# PX4FMUv2_4_6_0.net
KiCad netlist of a schematic drawn in Altium Designer
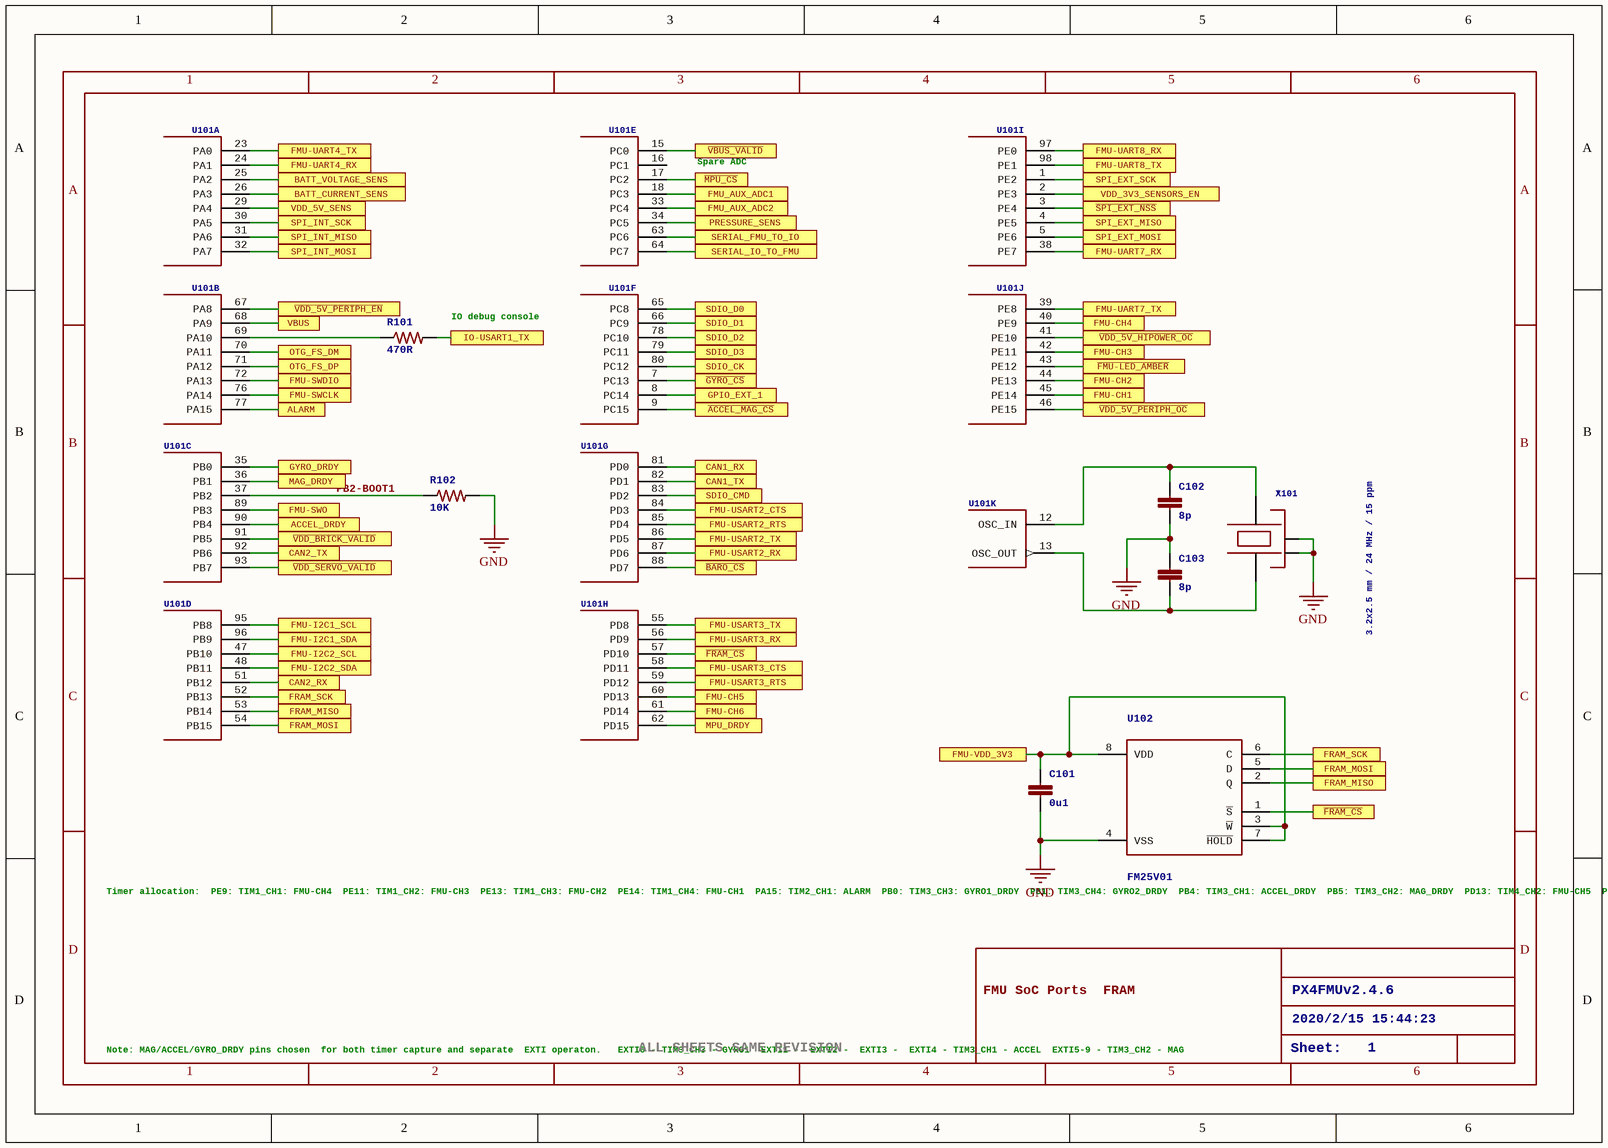
[diagram p0: PX4FMUv2.4.6_0.SchDoc]

(export (version "E")
  (design (tool "Eeschema 10.0.6"))
  (components
    (comp (ref "C101")
      (value "0u1")
      (footprint "0402-CAP")
      (description "CapacitorStandard 0603 ceramic capacitor, and 0.1\" leaded capacitor.")
      (fields (field (name "PARTNO") "CC0402ZRY5V7BB104"))
      (libsource (lib "pixhawk2") (part "CAP0402"))
    )
    (comp (ref "C102")
      (value "8p")
      (footprint "0402-CAP")
      (description "CapacitorStandard 0603 ceramic capacitor, and 0.1\" leaded capacitor.")
      (fields (field (name "PARTNO") "C1005C0G1H080C"))
      (libsource (lib "pixhawk2") (part "CAP0402"))
    )
    (comp (ref "C103")
      (value "8p")
      (footprint "0402-CAP")
      (description "CapacitorStandard 0603 ceramic capacitor, and 0.1\" leaded capacitor.")
      (fields (field (name "PARTNO") "C1005C0G1H080C"))
      (libsource (lib "pixhawk2") (part "CAP0402"))
    )
    (comp (ref "R101")
      (value "470R")
      (footprint "0402-RES")
      (fields (field (name "PARTNO") "RC0402FR-07470RL"))
      (libsource (lib "pixhawk2") (part "RESISTOR0402-RES"))
    )
    (comp (ref "R102")
      (value "10K")
      (footprint "0402-RES")
      (fields (field (name "PARTNO") "RC0402FR-0710KL"))
      (libsource (lib "pixhawk2") (part "RESISTOR0402-RES"))
    )
    (comp (ref "U101")
      (value "STM32F4X7VX")
      (footprint "TQFP100")
      (fields (field (name "PARTNO") "STM32F427VI"))
      (libsource (lib "pixhawk2") (part "STM32F4X7VX"))
    )
    (comp (ref "U102")
      (value "FM25V01")
      (footprint "SO08")
      (description "FM25V01 128Kb Serial 3V F-RAM Memory")
      (fields (field (name "PARTNO") "FM25V01-G"))
      (libsource (lib "pixhawk2") (part "FM25V01"))
    )
    (comp (ref "X101")
      (value "3.2x2.5 mm / 24 MHz / 15 ppm")
      (footprint "OSCILLATOR-3.2X2.5")
      (description "Crystal Oscillator in 3.2x2.5 SMD")
      (fields (field (name "NAME") "*") (field (name "PARTNO") "NX3225SA-24.000000MHZ"))
      (libsource (lib "pixhawk2") (part "OSCILLATOR-3.2X2.5"))
    )
  )
  (nets
    (net (code "1") (name "/ACCEL_DRDY") (class "Default")
      (node (ref "U101") (pin "90") (pinfunction "PB4_90") (pintype "passive"))
    )
    (net (code "2") (name "/ALARM") (class "Default")
      (node (ref "U101") (pin "77") (pinfunction "PA15_77") (pintype "passive"))
    )
    (net (code "3") (name "/BATT_CURRENT_SENS") (class "Default")
      (node (ref "U101") (pin "26") (pinfunction "PA3_26") (pintype "passive"))
    )
    (net (code "4") (name "/BATT_VOLTAGE_SENS") (class "Default")
      (node (ref "U101") (pin "25") (pinfunction "PA2_25") (pintype "passive"))
    )
    (net (code "5") (name "/CAN1_RX") (class "Default")
      (node (ref "U101") (pin "81") (pinfunction "PD0_81") (pintype "passive"))
    )
    (net (code "6") (name "/CAN1_TX") (class "Default")
      (node (ref "U101") (pin "82") (pinfunction "PD1_82") (pintype "passive"))
    )
    (net (code "7") (name "/CAN2_RX") (class "Default")
      (node (ref "U101") (pin "51") (pinfunction "PB12_51") (pintype "passive"))
    )
    (net (code "8") (name "/CAN2_TX") (class "Default")
      (node (ref "U101") (pin "92") (pinfunction "PB6_92") (pintype "passive"))
    )
    (net (code "9") (name "/FMU-CH1") (class "Default")
      (node (ref "U101") (pin "45") (pinfunction "PE14_45") (pintype "passive"))
    )
    (net (code "10") (name "/FMU-CH2") (class "Default")
      (node (ref "U101") (pin "44") (pinfunction "PE13_44") (pintype "passive"))
    )
    (net (code "11") (name "/FMU-CH3") (class "Default")
      (node (ref "U101") (pin "42") (pinfunction "PE11_42") (pintype "passive"))
    )
    (net (code "12") (name "/FMU-CH4") (class "Default")
      (node (ref "U101") (pin "40") (pinfunction "PE9_40") (pintype "passive"))
    )
    (net (code "13") (name "/FMU-CH5") (class "Default")
      (node (ref "U101") (pin "60") (pinfunction "PD13_60") (pintype "passive"))
    )
    (net (code "14") (name "/FMU-CH6") (class "Default")
      (node (ref "U101") (pin "61") (pinfunction "PD14_61") (pintype "passive"))
    )
    (net (code "15") (name "/FMU-I2C1_SCL") (class "Default")
      (node (ref "U101") (pin "95") (pinfunction "PB8_95") (pintype "passive"))
    )
    (net (code "16") (name "/FMU-I2C1_SDA") (class "Default")
      (node (ref "U101") (pin "96") (pinfunction "PB9_96") (pintype "passive"))
    )
    (net (code "17") (name "/FMU-I2C2_SCL") (class "Default")
      (node (ref "U101") (pin "47") (pinfunction "PB10_47") (pintype "passive"))
    )
    (net (code "18") (name "/FMU-I2C2_SDA") (class "Default")
      (node (ref "U101") (pin "48") (pinfunction "PB11_48") (pintype "passive"))
    )
    (net (code "19") (name "/FMU-SWCLK") (class "Default")
      (node (ref "U101") (pin "76") (pinfunction "PA14_76") (pintype "passive"))
    )
    (net (code "20") (name "/FMU-SWDIO") (class "Default")
      (node (ref "U101") (pin "72") (pinfunction "PA13_72") (pintype "passive"))
    )
    (net (code "21") (name "/FMU-SWO") (class "Default")
      (node (ref "U101") (pin "89") (pinfunction "PB3_89") (pintype "passive"))
    )
    (net (code "22") (name "/FMU-UART4_RX") (class "Default")
      (node (ref "U101") (pin "24") (pinfunction "PA1_24") (pintype "passive"))
    )
    (net (code "23") (name "/FMU-UART4_TX") (class "Default")
      (node (ref "U101") (pin "23") (pinfunction "PA0_23") (pintype "passive"))
    )
    (net (code "24") (name "/FMU-UART7_RX") (class "Default")
      (node (ref "U101") (pin "38") (pinfunction "PE7_38") (pintype "passive"))
    )
    (net (code "25") (name "/FMU-UART7_TX") (class "Default")
      (node (ref "U101") (pin "39") (pinfunction "PE8_39") (pintype "passive"))
    )
    (net (code "26") (name "/FMU-UART8_RX") (class "Default")
      (node (ref "U101") (pin "97") (pinfunction "PE0_97") (pintype "passive"))
    )
    (net (code "27") (name "/FMU-UART8_TX") (class "Default")
      (node (ref "U101") (pin "98") (pinfunction "PE1_98") (pintype "passive"))
    )
    (net (code "28") (name "/FMU-USART2_CTS") (class "Default")
      (node (ref "U101") (pin "84") (pinfunction "PD3_84") (pintype "passive"))
    )
    (net (code "29") (name "/FMU-USART2_RTS") (class "Default")
      (node (ref "U101") (pin "85") (pinfunction "PD4_85") (pintype "passive"))
    )
    (net (code "30") (name "/FMU-USART2_RX") (class "Default")
      (node (ref "U101") (pin "87") (pinfunction "PD6_87") (pintype "passive"))
    )
    (net (code "31") (name "/FMU-USART2_TX") (class "Default")
      (node (ref "U101") (pin "86") (pinfunction "PD5_86") (pintype "passive"))
    )
    (net (code "32") (name "/FMU-USART3_CTS") (class "Default")
      (node (ref "U101") (pin "58") (pinfunction "PD11_58") (pintype "passive"))
    )
    (net (code "33") (name "/FMU-USART3_RTS") (class "Default")
      (node (ref "U101") (pin "59") (pinfunction "PD12_59") (pintype "passive"))
    )
    (net (code "34") (name "/FMU-USART3_RX") (class "Default")
      (node (ref "U101") (pin "56") (pinfunction "PD9_56") (pintype "passive"))
    )
    (net (code "35") (name "/FMU-USART3_TX") (class "Default")
      (node (ref "U101") (pin "55") (pinfunction "PD8_55") (pintype "passive"))
    )
    (net (code "36") (name "/FMU-VDD_3V3") (class "Default")
      (node (ref "C101") (pin "P$1") (pinfunction "1_P$1") (pintype "passive"))
      (node (ref "U102") (pin "3") (pinfunction "~{W}_3") (pintype "passive"))
      (node (ref "U102") (pin "7") (pinfunction "~{HOLD}_7") (pintype "passive"))
      (node (ref "U102") (pin "8") (pinfunction "VDD_8") (pintype "passive"))
    )
    (net (code "37") (name "/FMU_AUX_ADC1") (class "Default")
      (node (ref "U101") (pin "18") (pinfunction "PC3_18") (pintype "passive"))
    )
    (net (code "38") (name "/FMU_AUX_ADC2") (class "Default")
      (node (ref "U101") (pin "33") (pinfunction "PC4_33") (pintype "passive"))
    )
    (net (code "39") (name "/FRAM_MISO") (class "Default")
      (node (ref "U101") (pin "53") (pinfunction "PB14_53") (pintype "passive"))
      (node (ref "U102") (pin "2") (pinfunction "Q_2") (pintype "passive"))
    )
    (net (code "40") (name "/FRAM_MOSI") (class "Default")
      (node (ref "U101") (pin "54") (pinfunction "PB15_54") (pintype "passive"))
      (node (ref "U102") (pin "5") (pinfunction "D_5") (pintype "passive"))
    )
    (net (code "41") (name "/FRAM_SCK") (class "Default")
      (node (ref "U101") (pin "52") (pinfunction "PB13_52") (pintype "passive"))
      (node (ref "U102") (pin "6") (pinfunction "C_6") (pintype "passive"))
    )
    (net (code "42") (name "/GPIO_EXT_1") (class "Default")
      (node (ref "U101") (pin "8") (pinfunction "PC14_8") (pintype "passive"))
    )
    (net (code "43") (name "/GYRO_DRDY") (class "Default")
      (node (ref "U101") (pin "35") (pinfunction "PB0_35") (pintype "passive"))
    )
    (net (code "44") (name "/IO-USART1_TX") (class "Default")
      (node (ref "R101") (pin "P$2") (pinfunction "2_P$2") (pintype "passive"))
    )
    (net (code "45") (name "/MAG_DRDY") (class "Default")
      (node (ref "U101") (pin "36") (pinfunction "PB1_36") (pintype "passive"))
    )
    (net (code "46") (name "/MPU_DRDY") (class "Default")
      (node (ref "U101") (pin "62") (pinfunction "PD15_62") (pintype "passive"))
    )
    (net (code "47") (name "/OTG_FS_DM") (class "Default")
      (node (ref "U101") (pin "70") (pinfunction "PA11_70") (pintype "passive"))
    )
    (net (code "48") (name "/OTG_FS_DP") (class "Default")
      (node (ref "U101") (pin "71") (pinfunction "PA12_71") (pintype "passive"))
    )
    (net (code "49") (name "/PB2-BOOT1") (class "Default")
      (node (ref "R102") (pin "P$1") (pinfunction "1_P$1") (pintype "passive"))
      (node (ref "U101") (pin "37") (pinfunction "PB2_37") (pintype "passive"))
    )
    (net (code "50") (name "/PRESSURE_SENS") (class "Default")
      (node (ref "U101") (pin "34") (pinfunction "PC5_34") (pintype "passive"))
    )
    (net (code "51") (name "/SDIO_CK") (class "Default")
      (node (ref "U101") (pin "80") (pinfunction "PC12_80") (pintype "passive"))
    )
    (net (code "52") (name "/SDIO_CMD") (class "Default")
      (node (ref "U101") (pin "83") (pinfunction "PD2_83") (pintype "passive"))
    )
    (net (code "53") (name "/SDIO_D0") (class "Default")
      (node (ref "U101") (pin "65") (pinfunction "PC8_65") (pintype "passive"))
    )
    (net (code "54") (name "/SDIO_D1") (class "Default")
      (node (ref "U101") (pin "66") (pinfunction "PC9_66") (pintype "passive"))
    )
    (net (code "55") (name "/SDIO_D2") (class "Default")
      (node (ref "U101") (pin "78") (pinfunction "PC10_78") (pintype "passive"))
    )
    (net (code "56") (name "/SDIO_D3") (class "Default")
      (node (ref "U101") (pin "79") (pinfunction "PC11_79") (pintype "passive"))
    )
    (net (code "57") (name "/SERIAL_FMU_TO_IO") (class "Default")
      (node (ref "U101") (pin "63") (pinfunction "PC6_63") (pintype "passive"))
    )
    (net (code "58") (name "/SERIAL_IO_TO_FMU") (class "Default")
      (node (ref "U101") (pin "64") (pinfunction "PC7_64") (pintype "passive"))
    )
    (net (code "59") (name "/SPI_EXT_MISO") (class "Default")
      (node (ref "U101") (pin "4") (pinfunction "PE5_4") (pintype "passive"))
    )
    (net (code "60") (name "/SPI_EXT_MOSI") (class "Default")
      (node (ref "U101") (pin "5") (pinfunction "PE6_5") (pintype "passive"))
    )
    (net (code "61") (name "/SPI_EXT_SCK") (class "Default")
      (node (ref "U101") (pin "1") (pinfunction "PE2_1") (pintype "passive"))
    )
    (net (code "62") (name "/SPI_INT_MISO") (class "Default")
      (node (ref "U101") (pin "31") (pinfunction "PA6_31") (pintype "passive"))
    )
    (net (code "63") (name "/SPI_INT_MOSI") (class "Default")
      (node (ref "U101") (pin "32") (pinfunction "PA7_32") (pintype "passive"))
    )
    (net (code "64") (name "/SPI_INT_SCK") (class "Default")
      (node (ref "U101") (pin "30") (pinfunction "PA5_30") (pintype "passive"))
    )
    (net (code "65") (name "/VBUS") (class "Default")
      (node (ref "U101") (pin "68") (pinfunction "PA9_68") (pintype "passive"))
    )
    (net (code "66") (name "/VDD_3V3_SENSORS_EN") (class "Default")
      (node (ref "U101") (pin "2") (pinfunction "PE3_2") (pintype "passive"))
    )
    (net (code "67") (name "/VDD_5V_SENS") (class "Default")
      (node (ref "U101") (pin "29") (pinfunction "PA4_29") (pintype "passive"))
    )
    (net (code "68") (name "/~{ACCEL_MAG_CS}") (class "Default")
      (node (ref "U101") (pin "9") (pinfunction "PC15_9") (pintype "passive"))
    )
    (net (code "69") (name "/~{BARO_CS}") (class "Default")
      (node (ref "U101") (pin "88") (pinfunction "PD7_88") (pintype "passive"))
    )
    (net (code "70") (name "/~{FMU-LED_AMBER}") (class "Default")
      (node (ref "U101") (pin "43") (pinfunction "PE12_43") (pintype "passive"))
    )
    (net (code "71") (name "/~{FRAM_CS}") (class "Default")
      (node (ref "U101") (pin "57") (pinfunction "PD10_57") (pintype "passive"))
      (node (ref "U102") (pin "1") (pinfunction "~{S}_1") (pintype "passive"))
    )
    (net (code "72") (name "/~{GYRO_CS}") (class "Default")
      (node (ref "U101") (pin "7") (pinfunction "PC13_7") (pintype "passive"))
    )
    (net (code "73") (name "/~{MPU_CS}") (class "Default")
      (node (ref "U101") (pin "17") (pinfunction "PC2_17") (pintype "passive"))
    )
    (net (code "74") (name "/~{SPI_EXT_NSS}") (class "Default")
      (node (ref "U101") (pin "3") (pinfunction "PE4_3") (pintype "passive"))
    )
    (net (code "75") (name "/~{VBUS_VALID}") (class "Default")
      (node (ref "U101") (pin "15") (pinfunction "PC0_15") (pintype "passive"))
    )
    (net (code "76") (name "/~{VDD_5V_HIPOWER_OC}") (class "Default")
      (node (ref "U101") (pin "41") (pinfunction "PE10_41") (pintype "passive"))
    )
    (net (code "77") (name "/~{VDD_5V_PERIPH_EN}") (class "Default")
      (node (ref "U101") (pin "67") (pinfunction "PA8_67") (pintype "passive"))
    )
    (net (code "78") (name "/~{VDD_5V_PERIPH_OC}") (class "Default")
      (node (ref "U101") (pin "46") (pinfunction "PE15_46") (pintype "passive"))
    )
    (net (code "79") (name "/~{VDD_BRICK_VALID}") (class "Default")
      (node (ref "U101") (pin "91") (pinfunction "PB5_91") (pintype "passive"))
    )
    (net (code "80") (name "/~{VDD_SERVO_VALID}") (class "Default")
      (node (ref "U101") (pin "93") (pinfunction "PB7_93") (pintype "passive"))
    )
    (net (code "81") (name "GND") (class "Default")
      (node (ref "C101") (pin "P$2") (pinfunction "2_P$2") (pintype "passive"))
      (node (ref "C102") (pin "P$2") (pinfunction "2_P$2") (pintype "passive"))
      (node (ref "C103") (pin "P$1") (pinfunction "1_P$1") (pintype "passive"))
      (node (ref "R102") (pin "P$2") (pinfunction "2_P$2") (pintype "passive"))
      (node (ref "U102") (pin "4") (pinfunction "VSS_4") (pintype "passive"))
      (node (ref "X101") (pin "2") (pinfunction "NC_2_2") (pintype "open_emitter"))
      (node (ref "X101") (pin "4") (pinfunction "NC_4_4") (pintype "open_emitter"))
    )
    (net (code "82") (name "Net-(C102-1)") (class "Default")
      (node (ref "C102") (pin "P$1") (pinfunction "1_P$1") (pintype "passive"))
      (node (ref "U101") (pin "12") (pinfunction "OSC_IN_12") (pintype "passive"))
      (node (ref "X101") (pin "3") (pinfunction "3_3") (pintype "passive"))
    )
    (net (code "83") (name "Net-(C103-2)") (class "Default")
      (node (ref "C103") (pin "P$2") (pinfunction "2_P$2") (pintype "passive"))
      (node (ref "U101") (pin "13") (pinfunction "OSC_OUT_13") (pintype "output"))
      (node (ref "X101") (pin "1") (pinfunction "1_1") (pintype "passive"))
    )
    (net (code "84") (name "Net-(R101-1)") (class "Default")
      (node (ref "R101") (pin "P$1") (pinfunction "1_P$1") (pintype "passive"))
      (node (ref "U101") (pin "69") (pinfunction "PA10_69") (pintype "passive"))
    )
    (net (code "85") (name "unconnected-(U101E-PC1-Pad16)") (class "Default")
      (node (ref "U101") (pin "16") (pinfunction "PC1_16") (pintype "passive"))
    )
  )
)
